# easyeda-schematic.net
KiCad netlist of a schematic drawn in EasyEDA
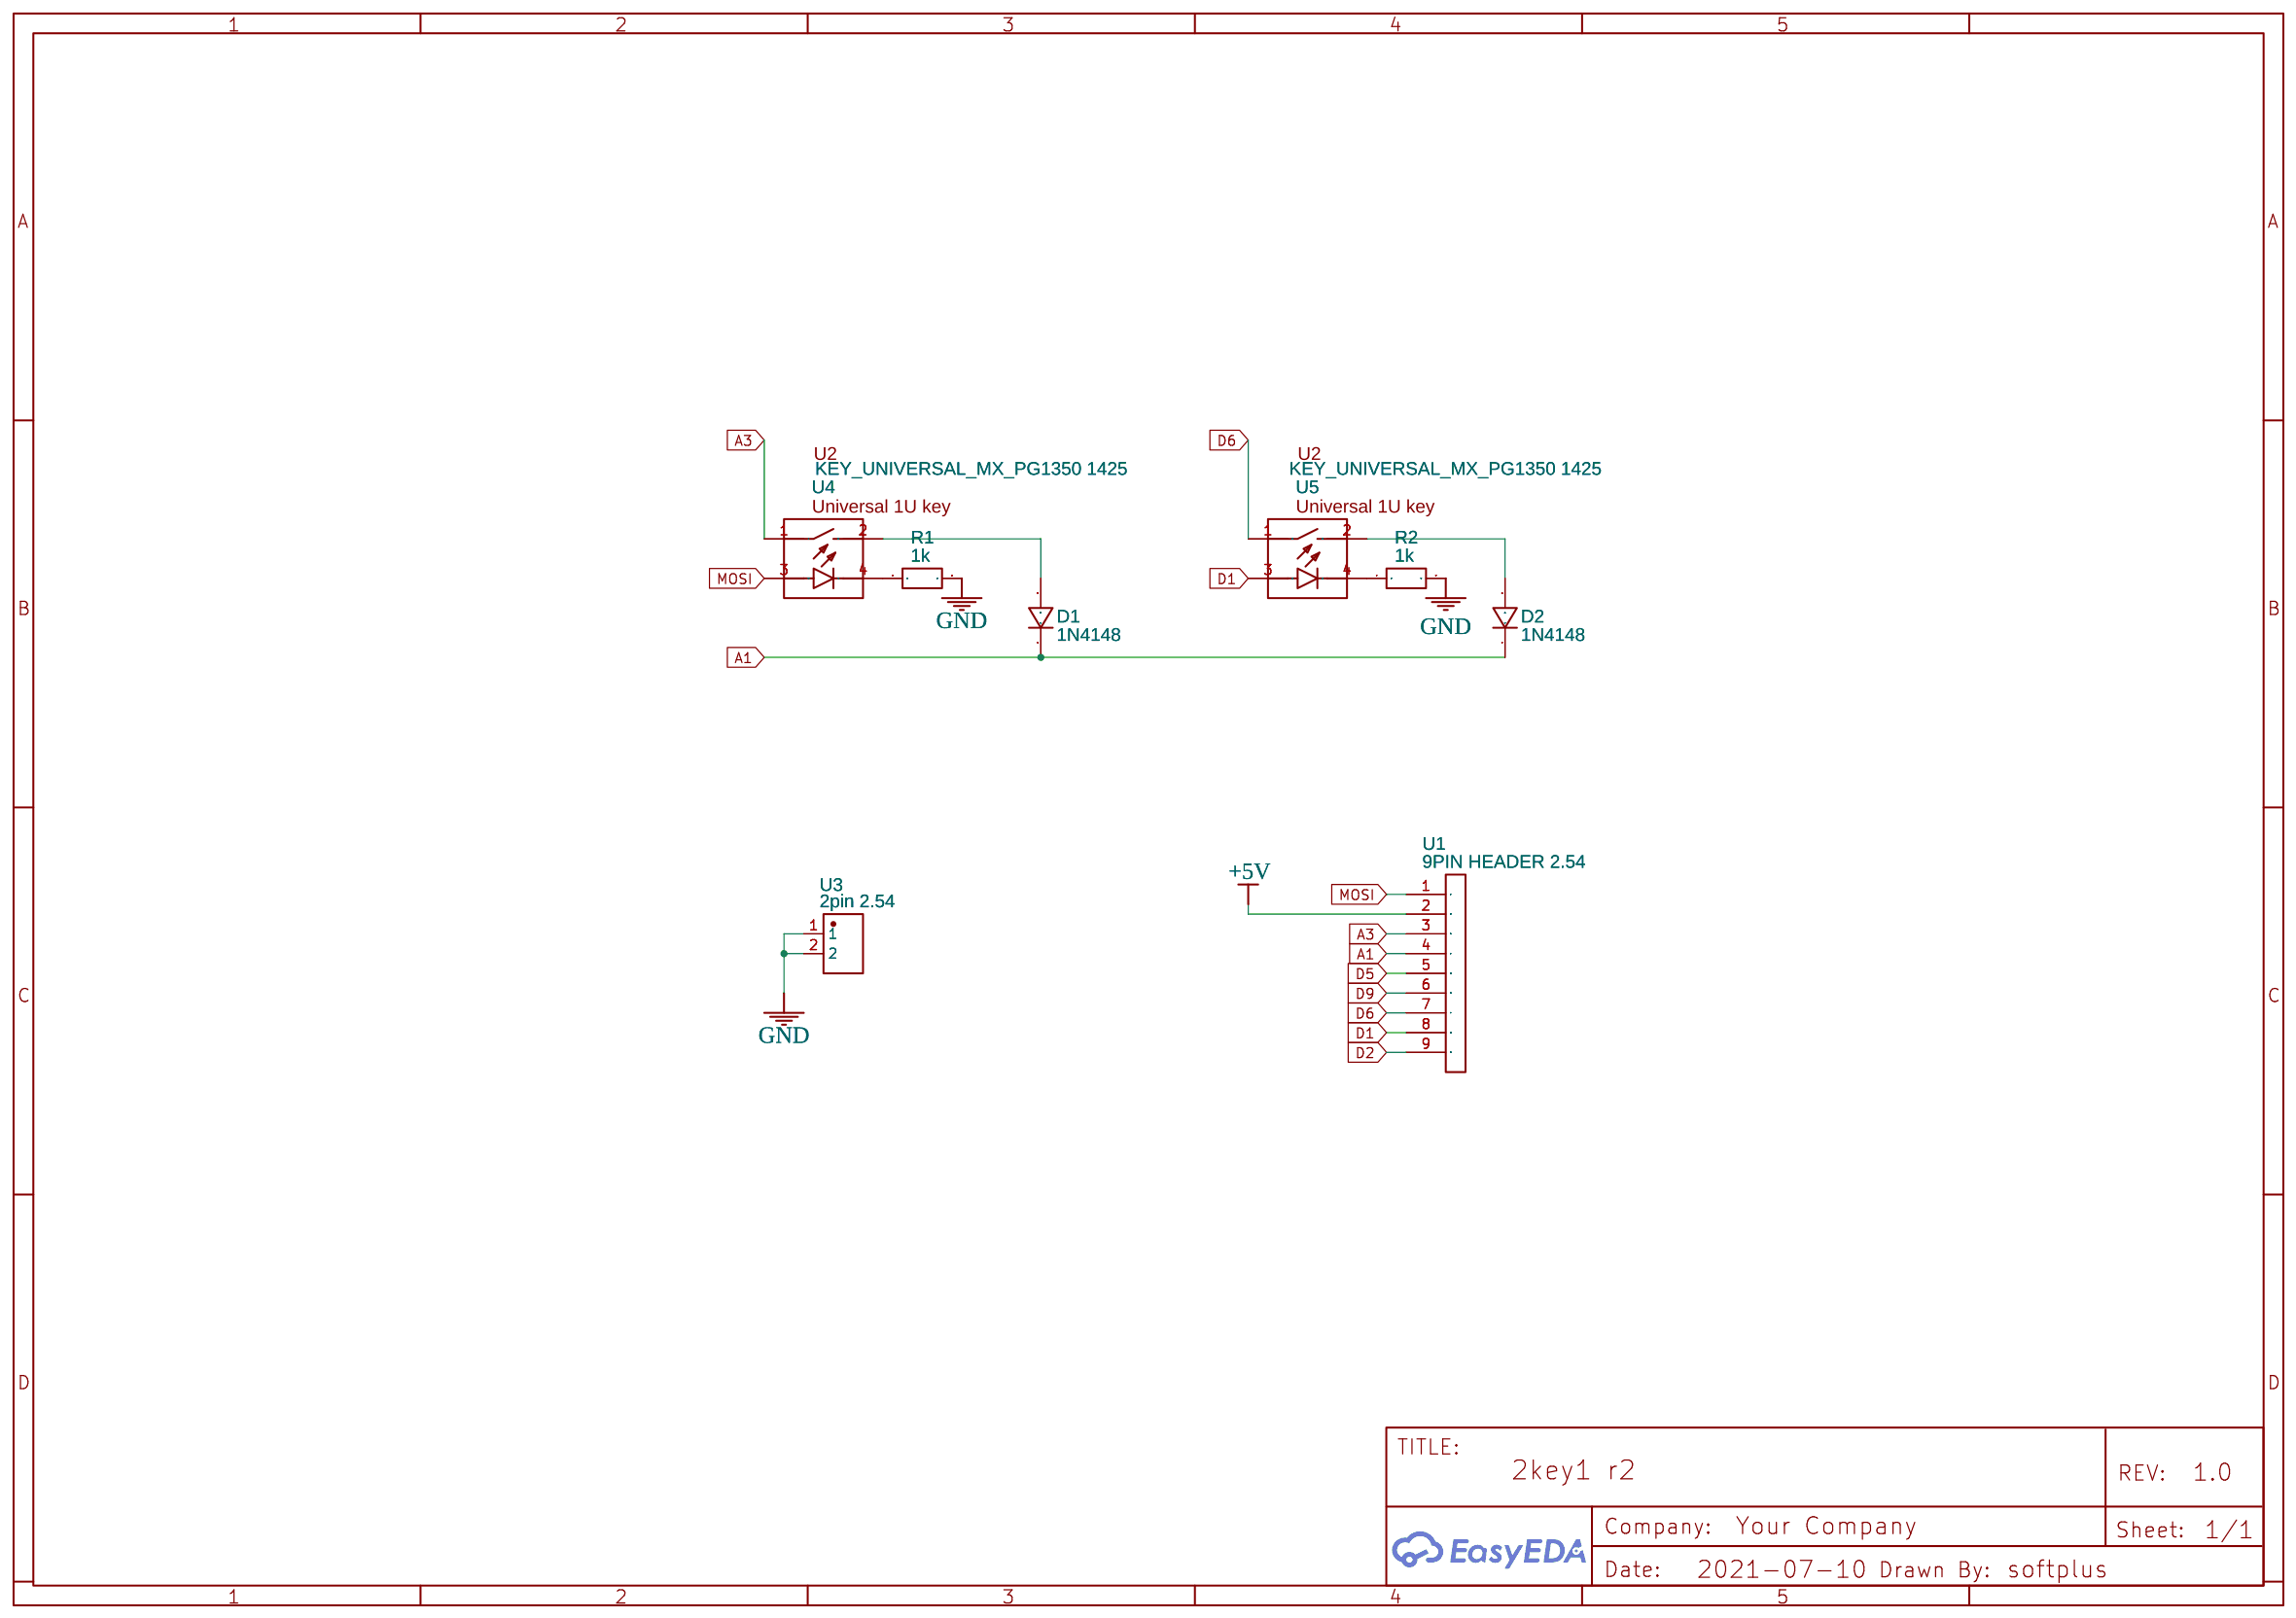
[diagram p0: schematic sheet]

(export (version "E")
  (design (tool "Eeschema 10.0.6"))
  (components
    (comp (ref "D1")
      (value "1N4148")
      (fields (field (name "BOM_Manufacturer Part") "1N4007W") (field (name "BOM_Supplier Part") "C328592"))
      (libsource (lib "") (part "1N4007W"))
    )
    (comp (ref "D2")
      (value "1N4148")
      (fields (field (name "BOM_Manufacturer Part") "1N4007W") (field (name "BOM_Supplier Part") "C328592"))
      (libsource (lib "") (part "1N4007W"))
    )
    (comp (ref "R1") (value "1k") (libsource (lib "") (part "R_0603_EU")))
    (comp (ref "R2") (value "1k") (libsource (lib "") (part "R_0603_EU")))
    (comp (ref "U1") (value "9PIN HEADER 2.54") (libsource (lib "") (part "9PIN HEADER 2.54")))
    (comp (ref "U3")
      (value "2pin 2.54")
      (fields (field (name "BOM_Manufacturer Part") "2pin"))
      (libsource (lib "") (part "2pin 2.54"))
    )
    (comp (ref "U4")
      (value "KEY_UNIVERSAL_MX_PG1350 1425")
      (libsource (lib "") (part "KEY_UNIVERSAL_MX_PG1350 1425"))
    )
    (comp (ref "U5")
      (value "KEY_UNIVERSAL_MX_PG1350 1425")
      (libsource (lib "") (part "KEY_UNIVERSAL_MX_PG1350 1425"))
    )
  )
  (nets
    (net (code "1") (name "+5V") (class "Default")
      (node (ref "U1") (pin "2") (pinfunction "2_2") (pintype "unspecified"))
    )
    (net (code "2") (name "A1") (class "Default")
      (node (ref "D1") (pin "1") (pinfunction "1_1") (pintype "unspecified"))
      (node (ref "D2") (pin "1") (pinfunction "1_1") (pintype "unspecified"))
      (node (ref "U1") (pin "4") (pinfunction "4_4") (pintype "unspecified"))
    )
    (net (code "3") (name "A3") (class "Default")
      (node (ref "U1") (pin "3") (pinfunction "3_3") (pintype "unspecified"))
      (node (ref "U4") (pin "1") (pinfunction "1_1") (pintype "unspecified"))
    )
    (net (code "4") (name "D1") (class "Default")
      (node (ref "U1") (pin "8") (pinfunction "8_8") (pintype "unspecified"))
      (node (ref "U5") (pin "3") (pinfunction "3_3") (pintype "unspecified"))
    )
    (net (code "5") (name "D2") (class "Default")
      (node (ref "U1") (pin "9") (pinfunction "9_9") (pintype "unspecified"))
    )
    (net (code "6") (name "D5") (class "Default")
      (node (ref "U1") (pin "5") (pinfunction "5_5") (pintype "unspecified"))
    )
    (net (code "7") (name "D6") (class "Default")
      (node (ref "U1") (pin "7") (pinfunction "7_7") (pintype "unspecified"))
      (node (ref "U5") (pin "1") (pinfunction "1_1") (pintype "unspecified"))
    )
    (net (code "8") (name "D9") (class "Default")
      (node (ref "U1") (pin "6") (pinfunction "6_6") (pintype "unspecified"))
    )
    (net (code "9") (name "GND") (class "Default")
      (node (ref "R1") (pin "2") (pinfunction "2_2") (pintype "unspecified"))
      (node (ref "R2") (pin "2") (pinfunction "2_2") (pintype "unspecified"))
      (node (ref "U3") (pin "1") (pinfunction "1_1") (pintype "unspecified"))
      (node (ref "U3") (pin "2") (pinfunction "2_2") (pintype "unspecified"))
    )
    (net (code "10") (name "MOSI") (class "Default")
      (node (ref "U1") (pin "1") (pinfunction "1_1") (pintype "unspecified"))
      (node (ref "U4") (pin "3") (pinfunction "3_3") (pintype "unspecified"))
    )
    (net (code "11") (name "Net-(D1-Pad2)") (class "Default")
      (node (ref "D1") (pin "2") (pinfunction "2_2") (pintype "unspecified"))
      (node (ref "U4") (pin "2") (pinfunction "2_2") (pintype "unspecified"))
    )
    (net (code "12") (name "Net-(D2-Pad2)") (class "Default")
      (node (ref "D2") (pin "2") (pinfunction "2_2") (pintype "unspecified"))
      (node (ref "U5") (pin "2") (pinfunction "2_2") (pintype "unspecified"))
    )
    (net (code "13") (name "Net-(R1-Pad1)") (class "Default")
      (node (ref "R1") (pin "1") (pinfunction "1_1") (pintype "unspecified"))
      (node (ref "U4") (pin "4") (pinfunction "4_4") (pintype "unspecified"))
    )
    (net (code "14") (name "Net-(R2-Pad1)") (class "Default")
      (node (ref "R2") (pin "1") (pinfunction "1_1") (pintype "unspecified"))
      (node (ref "U5") (pin "4") (pinfunction "4_4") (pintype "unspecified"))
    )
  )
)
